# Crystals.net
KiCad netlist of a schematic drawn in Altium Designer
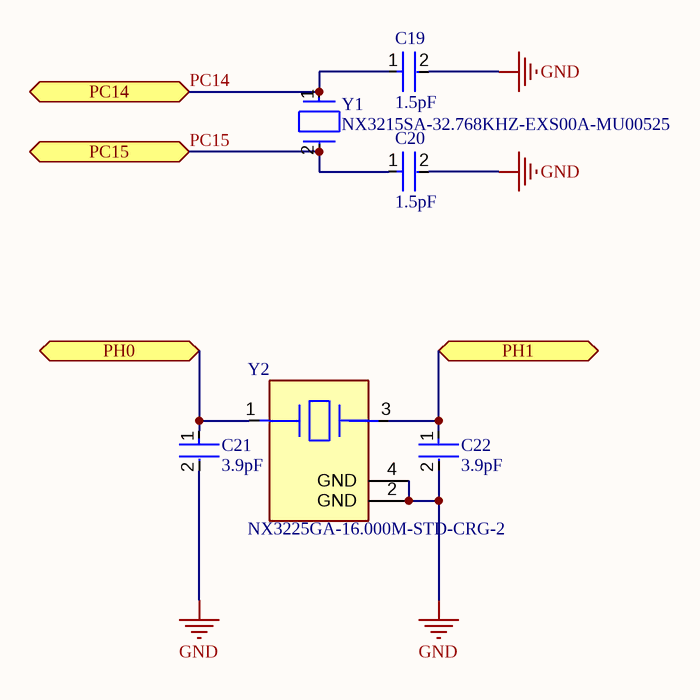
[diagram p0: Crystals.SchDoc]

(export (version "E")
  (design (tool "Eeschema 10.0.6"))
  (components
    (comp (ref "C19")
      (value "1.5pF")
      (footprint "FP-C0603C-CF-MFG")
      (description "CAP CER 1.5PF 100V NP0 0603")
      (fields
        (field (name "MANUFACTURER PART NUMBER") "C0603C159C1GACTU")
        (field (name "TOLERANCE") "0.25 pF")
      )
      (libsource (lib "Altium Content Vault") (part "b4654b650e69147ec39a6b967a45e02"))
    )
    (comp (ref "C20")
      (value "1.5pF")
      (footprint "FP-C0603C-CF-MFG")
      (description "CAP CER 1.5PF 100V NP0 0603")
      (fields
        (field (name "MANUFACTURER PART NUMBER") "C0603C159C1GACTU")
        (field (name "TOLERANCE") "0.25 pF")
      )
      (libsource (lib "Altium Content Vault") (part "b4654b650e69147ec39a6b967a45e02"))
    )
    (comp (ref "C21")
      (value "3.9pF")
      (footprint "FP-CBR06C-MFG")
      (description "CAP CER 3.9PF 250V C0G/NP0 0603")
      (fields
        (field (name "OCTOPART") "https://octopart.com/cbr06c399cagac-kemet-20446767")
        (field (name "MANUFACTURER PART NUMBER") "CBR06C399CAGAC")
      )
      (libsource (lib "Altium Content Vault") (part "11868f565c42a9108669ba33697ecf6"))
    )
    (comp (ref "C22")
      (value "3.9pF")
      (footprint "FP-CBR06C-MFG")
      (description "CAP CER 3.9PF 250V C0G/NP0 0603")
      (fields
        (field (name "OCTOPART") "https://octopart.com/cbr06c399cagac-kemet-20446767")
        (field (name "MANUFACTURER PART NUMBER") "CBR06C399CAGAC")
      )
      (libsource (lib "Altium Content Vault") (part "11868f565c42a9108669ba33697ecf6"))
    )
    (comp (ref "Y1")
      (value "NX3215SA-32.768KHZ-EXS00A-MU00525")
      (footprint "FP-NX3215SA-MFG")
      (description "CRYSTAL 32.7680KHZ 6PF SMD")
      (libsource (lib "Altium Content Vault") (part "c23a69dc6c9e2f18f2079038eb95dd1"))
    )
    (comp (ref "Y2")
      (value "NX3225GA-16.000M-STD-CRG-2")
      (footprint "FP-NX3225GA-MFG")
      (description "CRYSTAL 16.0000MHZ 8PF SMD")
      (libsource (lib "Altium Content Vault") (part "6320effb7d3e443b36bf79d8ebe02e5"))
    )
  )
  (nets
    (net (code "1") (name "/PC14") (class "Default")
      (node (ref "C19") (pin "1") (pinfunction "1_1") (pintype "passive"))
      (node (ref "Y1") (pin "1") (pinfunction "1_1") (pintype "passive"))
    )
    (net (code "2") (name "/PC15") (class "Default")
      (node (ref "C20") (pin "1") (pinfunction "1_1") (pintype "passive"))
      (node (ref "Y1") (pin "2") (pinfunction "2_2") (pintype "passive"))
    )
    (net (code "3") (name "/PH0") (class "Default")
      (node (ref "C21") (pin "1") (pinfunction "1_1") (pintype "passive"))
      (node (ref "Y2") (pin "1") (pinfunction "1_1") (pintype "passive"))
    )
    (net (code "4") (name "/PH1") (class "Default")
      (node (ref "C22") (pin "1") (pinfunction "1_1") (pintype "passive"))
      (node (ref "Y2") (pin "3") (pinfunction "3_3") (pintype "passive"))
    )
    (net (code "5") (name "GND") (class "Default")
      (node (ref "C19") (pin "2") (pinfunction "2_2") (pintype "passive"))
      (node (ref "C20") (pin "2") (pinfunction "2_2") (pintype "passive"))
      (node (ref "C21") (pin "2") (pinfunction "2_2") (pintype "passive"))
      (node (ref "C22") (pin "2") (pinfunction "2_2") (pintype "passive"))
      (node (ref "Y2") (pin "2") (pinfunction "GND_2") (pintype "power_in"))
      (node (ref "Y2") (pin "4") (pinfunction "GND_4") (pintype "power_in"))
    )
  )
)
